# powerboard.net
KiCad netlist of a schematic drawn in EAGLE
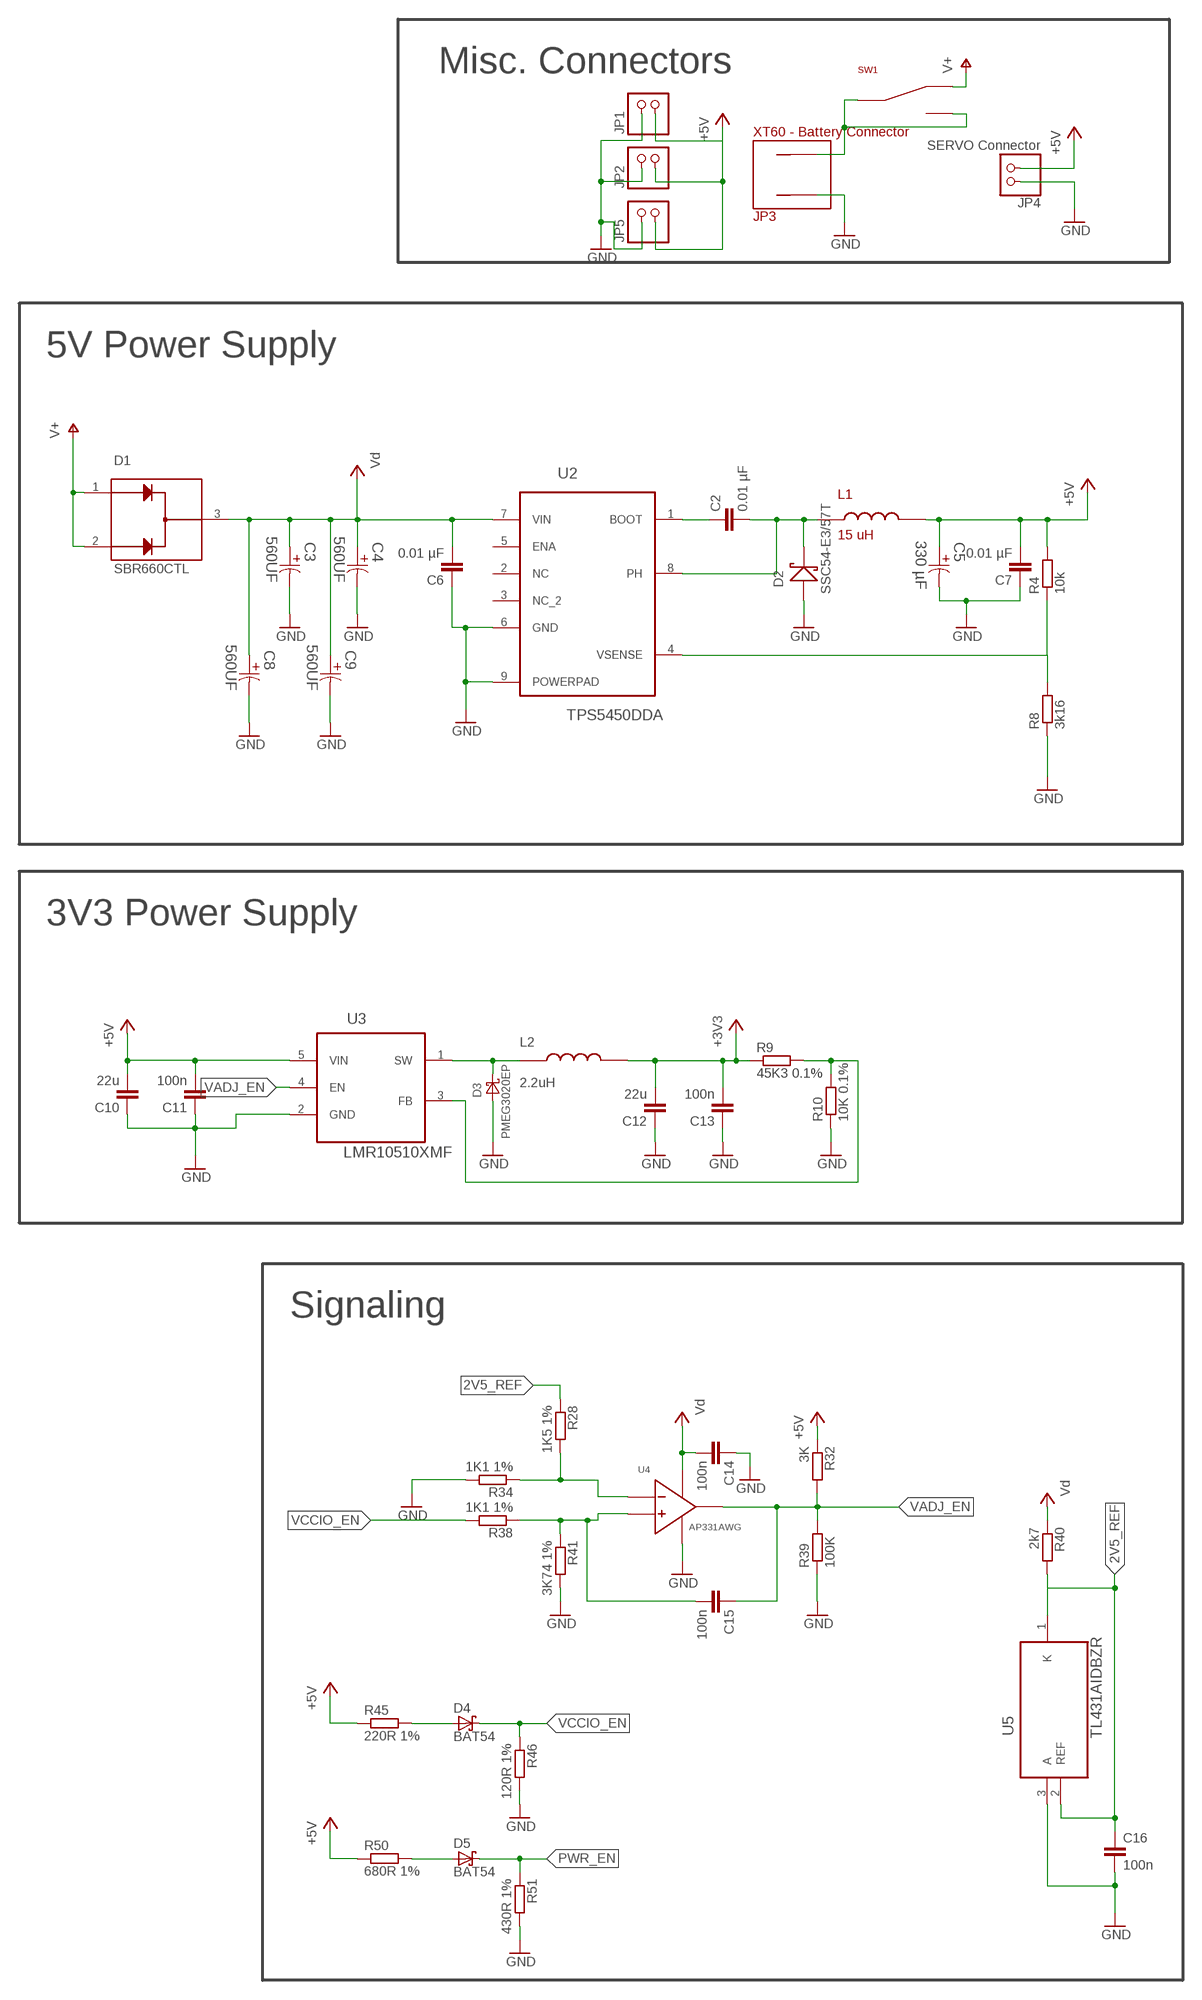
[diagram p0: schematic, sheet 1, part 1 of 2]
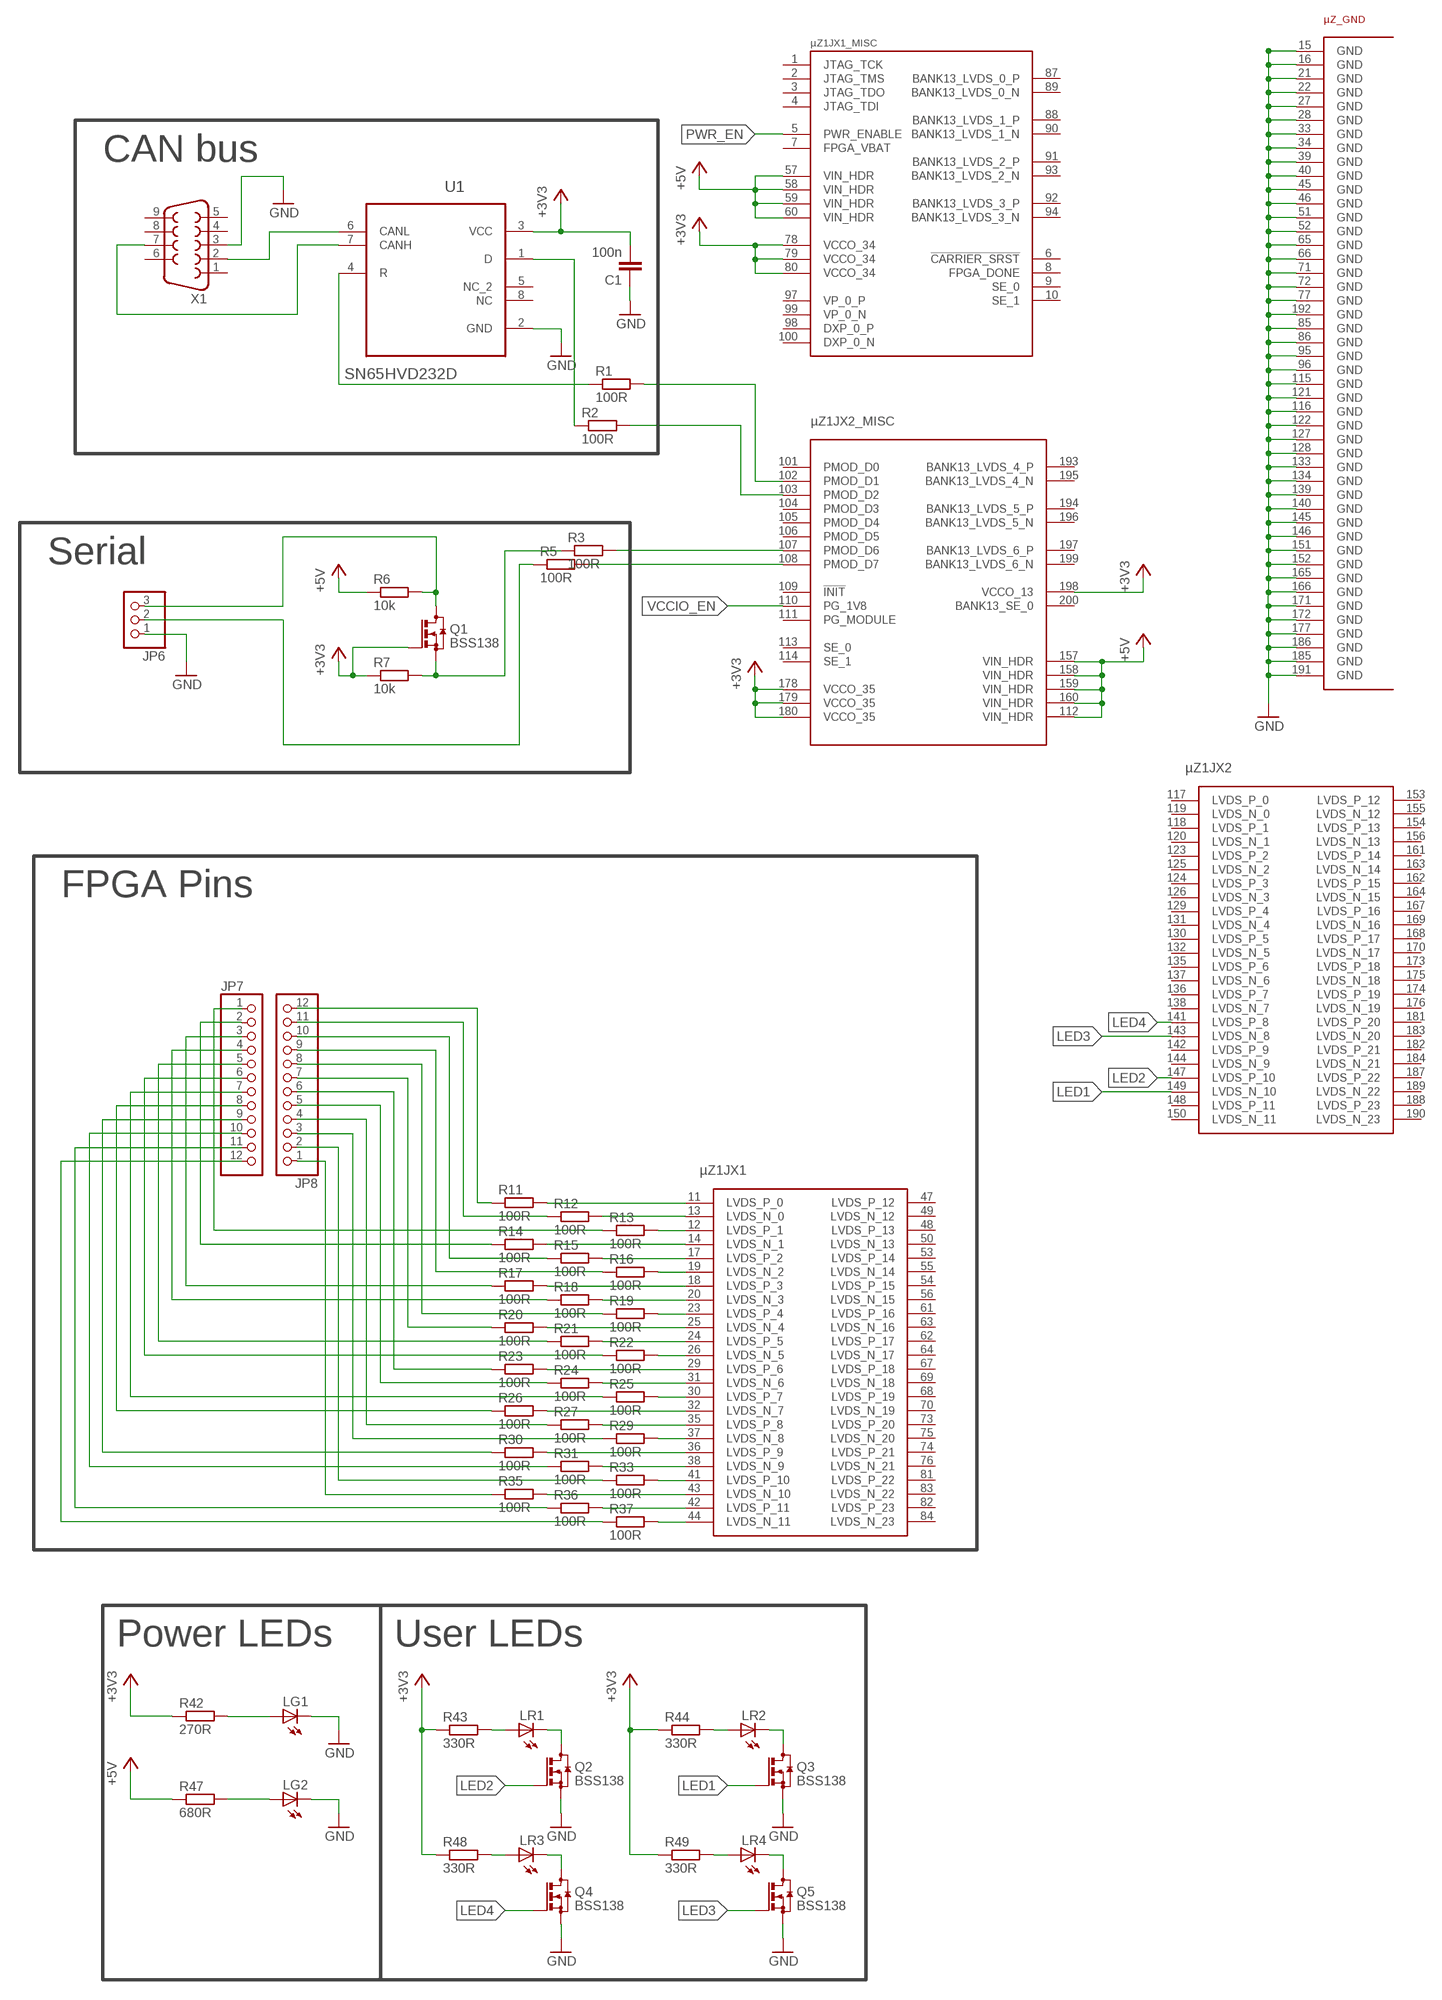
[diagram p1: schematic, sheet 1, part 2 of 2]

(export (version "E")
  (design (tool "Eeschema 10.0.6"))
  (components
    (comp (ref "C1")
      (value "100n")
      (footprint "eagle-import:C0805")
      (libsource (lib "eagle-import") (part "C-EUC0805"))
    )
    (comp (ref "C2")
      (value "0.01 µF")
      (footprint "eagle-import:C0805")
      (libsource (lib "eagle-import") (part "C-EUC0805"))
    )
    (comp (ref "C3")
      (value "560UF")
      (footprint "eagle-import:CAPAE1030X1050N")
      (fields (field (name "MPN") "EEE-FT1V561AP") (field (name "TOLERANCE") "±20 %"))
      (libsource (lib "eagle-import") (part "EEE--CASE-GFT1V561AP"))
    )
    (comp (ref "C4")
      (value "560UF")
      (footprint "eagle-import:CAPAE1030X1050N")
      (fields (field (name "MPN") "EEE-FT1V561AP") (field (name "TOLERANCE") "±20 %"))
      (libsource (lib "eagle-import") (part "EEE--CASE-GFT1V561AP"))
    )
    (comp (ref "C5")
      (value "330 µF")
      (footprint "eagle-import:CAPAE660X800N")
      (fields (field (name "MPN") "EEE-FTC331XAP") (field (name "TOLERANCE") "±20 %"))
      (libsource (lib "eagle-import") (part "EEE--CASE-D8FTC331XAP"))
    )
    (comp (ref "C6")
      (value "0.01 µF")
      (footprint "eagle-import:C0805")
      (libsource (lib "eagle-import") (part "C-EUC0805"))
    )
    (comp (ref "C7")
      (value "0.01 µF")
      (footprint "eagle-import:C0805")
      (libsource (lib "eagle-import") (part "C-EUC0805"))
    )
    (comp (ref "C8")
      (value "560UF")
      (footprint "eagle-import:CAPAE1030X1050N")
      (fields (field (name "MPN") "EEE-FT1V561AP") (field (name "TOLERANCE") "±20 %"))
      (libsource (lib "eagle-import") (part "EEE--CASE-GFT1V561AP"))
    )
    (comp (ref "C9")
      (value "560UF")
      (footprint "eagle-import:CAPAE1030X1050N")
      (fields (field (name "MPN") "EEE-FT1V561AP") (field (name "TOLERANCE") "±20 %"))
      (libsource (lib "eagle-import") (part "EEE--CASE-GFT1V561AP"))
    )
    (comp (ref "C10")
      (value "22u")
      (footprint "eagle-import:C0805")
      (libsource (lib "eagle-import") (part "C-EUC0805"))
    )
    (comp (ref "C11")
      (value "100n")
      (footprint "eagle-import:C0805")
      (libsource (lib "eagle-import") (part "C-EUC0805"))
    )
    (comp (ref "C12")
      (value "22u")
      (footprint "eagle-import:C0805")
      (libsource (lib "eagle-import") (part "C-EUC0805"))
    )
    (comp (ref "C13")
      (value "100n")
      (footprint "eagle-import:C0805")
      (libsource (lib "eagle-import") (part "C-EUC0805"))
    )
    (comp (ref "C14")
      (value "100n")
      (footprint "eagle-import:C0805")
      (libsource (lib "eagle-import") (part "C-EUC0805"))
    )
    (comp (ref "C15")
      (value "100n")
      (footprint "eagle-import:C0805")
      (libsource (lib "eagle-import") (part "C-EUC0805"))
    )
    (comp (ref "C16")
      (value "100n")
      (footprint "eagle-import:C0805")
      (libsource (lib "eagle-import") (part "C-EUC0805"))
    )
    (comp (ref "D1")
      (value "SBR660CTL")
      (footprint "eagle-import:TO252")
      (libsource (lib "eagle-import") (part "SBR660CTL"))
    )
    (comp (ref "D2")
      (value "SSC54-E3/57T")
      (footprint "eagle-import:DO-214AB")
      (fields (field (name "MANUFACTURER") "Comchip Technology") (field (name "PART_NUMBER") "CDBC540-G"))
      (libsource (lib "eagle-import") (part "CDBC540-G"))
    )
    (comp (ref "D3")
      (value "PMEG3020EP")
      (footprint "eagle-import:SOD128")
      (libsource (lib "eagle-import") (part "DIODE-SCHOTTKY-SOD128"))
    )
    (comp (ref "D4")
      (value "BAT54")
      (footprint "eagle-import:SOT23")
      (libsource (lib "eagle-import") (part "BAT54"))
    )
    (comp (ref "D5")
      (value "BAT54")
      (footprint "eagle-import:SOT23")
      (libsource (lib "eagle-import") (part "BAT54"))
    )
    (comp (ref "JP1")
      (value "PINHD-1X2")
      (footprint "eagle-import:CUST")
      (libsource (lib "eagle-import") (part "PINHD-1X2"))
    )
    (comp (ref "JP2")
      (value "PINHD-1X2")
      (footprint "eagle-import:CUST")
      (libsource (lib "eagle-import") (part "PINHD-1X2"))
    )
    (comp (ref "JP3")
      (value "XT60 - Battery Connector")
      (footprint "eagle-import:XT60")
      (libsource (lib "eagle-import") (part "XT60"))
    )
    (comp (ref "JP4")
      (value "SERVO Connector")
      (footprint "eagle-import:1X02_90")
      (libsource (lib "eagle-import") (part "PINHD-1X2/90"))
    )
    (comp (ref "JP5")
      (value "PINHD-1X2")
      (footprint "eagle-import:CUST")
      (libsource (lib "eagle-import") (part "PINHD-1X2"))
    )
    (comp (ref "JP6")
      (value "PINHD-1X3")
      (footprint "eagle-import:1X03")
      (libsource (lib "eagle-import") (part "PINHD-1X3"))
    )
    (comp (ref "JP7")
      (value "PINHD-1X12")
      (footprint "eagle-import:1X12")
      (libsource (lib "eagle-import") (part "PINHD-1X12"))
    )
    (comp (ref "JP8")
      (value "PINHD-1X12")
      (footprint "eagle-import:1X12")
      (libsource (lib "eagle-import") (part "PINHD-1X12"))
    )
    (comp (ref "L1")
      (value "15 uH")
      (footprint "eagle-import:BOURNS")
      (libsource (lib "eagle-import") (part "BOURNS-POWER-IND"))
    )
    (comp (ref "L2")
      (value "2.2uH")
      (footprint "eagle-import:INDZYNQ2")
      (libsource (lib "eagle-import") (part "INDZYNQNEW"))
    )
    (comp (ref "LG1")
      (value "LEDCHIP-LED0805")
      (footprint "eagle-import:CHIP-LED0805")
      (libsource (lib "eagle-import") (part "LEDCHIP-LED0805"))
    )
    (comp (ref "LG2")
      (value "LEDCHIP-LED0805")
      (footprint "eagle-import:CHIP-LED0805")
      (libsource (lib "eagle-import") (part "LEDCHIP-LED0805"))
    )
    (comp (ref "LR1")
      (value "LEDCHIP-LED0805")
      (footprint "eagle-import:CHIP-LED0805")
      (libsource (lib "eagle-import") (part "LEDCHIP-LED0805"))
    )
    (comp (ref "LR2")
      (value "LEDCHIP-LED0805")
      (footprint "eagle-import:CHIP-LED0805")
      (libsource (lib "eagle-import") (part "LEDCHIP-LED0805"))
    )
    (comp (ref "LR3")
      (value "LEDCHIP-LED0805")
      (footprint "eagle-import:CHIP-LED0805")
      (libsource (lib "eagle-import") (part "LEDCHIP-LED0805"))
    )
    (comp (ref "LR4")
      (value "LEDCHIP-LED0805")
      (footprint "eagle-import:CHIP-LED0805")
      (libsource (lib "eagle-import") (part "LEDCHIP-LED0805"))
    )
    (comp (ref "Q1")
      (value "BSS138")
      (footprint "eagle-import:SOT23")
      (libsource (lib "eagle-import") (part "BSS123"))
    )
    (comp (ref "Q2")
      (value "BSS138")
      (footprint "eagle-import:SOT23")
      (libsource (lib "eagle-import") (part "BSS123"))
    )
    (comp (ref "Q3")
      (value "BSS138")
      (footprint "eagle-import:SOT23")
      (libsource (lib "eagle-import") (part "BSS123"))
    )
    (comp (ref "Q4")
      (value "BSS138")
      (footprint "eagle-import:SOT23")
      (libsource (lib "eagle-import") (part "BSS123"))
    )
    (comp (ref "Q5")
      (value "BSS138")
      (footprint "eagle-import:SOT23")
      (libsource (lib "eagle-import") (part "BSS123"))
    )
    (comp (ref "R1")
      (value "100R")
      (footprint "eagle-import:R0805")
      (libsource (lib "eagle-import") (part "R-EU_R0805"))
    )
    (comp (ref "R2")
      (value "100R")
      (footprint "eagle-import:R0805")
      (libsource (lib "eagle-import") (part "R-EU_R0805"))
    )
    (comp (ref "R3")
      (value "100R")
      (footprint "eagle-import:R0805")
      (libsource (lib "eagle-import") (part "R-EU_R0805"))
    )
    (comp (ref "R4")
      (value "10k")
      (footprint "eagle-import:R0805")
      (libsource (lib "eagle-import") (part "R-EU_R0805"))
    )
    (comp (ref "R5")
      (value "100R")
      (footprint "eagle-import:R0805")
      (libsource (lib "eagle-import") (part "R-EU_R0805"))
    )
    (comp (ref "R6")
      (value "10k")
      (footprint "eagle-import:R0805")
      (libsource (lib "eagle-import") (part "R-EU_R0805"))
    )
    (comp (ref "R7")
      (value "10k")
      (footprint "eagle-import:R0805")
      (libsource (lib "eagle-import") (part "R-EU_R0805"))
    )
    (comp (ref "R8")
      (value "3k16")
      (footprint "eagle-import:R0805")
      (libsource (lib "eagle-import") (part "R-EU_R0805"))
    )
    (comp (ref "R9")
      (value "45K3 0.1%")
      (footprint "eagle-import:R0805")
      (libsource (lib "eagle-import") (part "R-EU_R0805"))
    )
    (comp (ref "R10")
      (value "10K 0.1%")
      (footprint "eagle-import:R0805")
      (libsource (lib "eagle-import") (part "R-EU_R0805"))
    )
    (comp (ref "R11")
      (value "100R")
      (footprint "eagle-import:R0805")
      (libsource (lib "eagle-import") (part "R-EU_R0805"))
    )
    (comp (ref "R12")
      (value "100R")
      (footprint "eagle-import:R0805")
      (libsource (lib "eagle-import") (part "R-EU_R0805"))
    )
    (comp (ref "R13")
      (value "100R")
      (footprint "eagle-import:R0805")
      (libsource (lib "eagle-import") (part "R-EU_R0805"))
    )
    (comp (ref "R14")
      (value "100R")
      (footprint "eagle-import:R0805")
      (libsource (lib "eagle-import") (part "R-EU_R0805"))
    )
    (comp (ref "R15")
      (value "100R")
      (footprint "eagle-import:R0805")
      (libsource (lib "eagle-import") (part "R-EU_R0805"))
    )
    (comp (ref "R16")
      (value "100R")
      (footprint "eagle-import:R0805")
      (libsource (lib "eagle-import") (part "R-EU_R0805"))
    )
    (comp (ref "R17")
      (value "100R")
      (footprint "eagle-import:R0805")
      (libsource (lib "eagle-import") (part "R-EU_R0805"))
    )
    (comp (ref "R18")
      (value "100R")
      (footprint "eagle-import:R0805")
      (libsource (lib "eagle-import") (part "R-EU_R0805"))
    )
    (comp (ref "R19")
      (value "100R")
      (footprint "eagle-import:R0805")
      (libsource (lib "eagle-import") (part "R-EU_R0805"))
    )
    (comp (ref "R20")
      (value "100R")
      (footprint "eagle-import:R0805")
      (libsource (lib "eagle-import") (part "R-EU_R0805"))
    )
    (comp (ref "R21")
      (value "100R")
      (footprint "eagle-import:R0805")
      (libsource (lib "eagle-import") (part "R-EU_R0805"))
    )
    (comp (ref "R22")
      (value "100R")
      (footprint "eagle-import:R0805")
      (libsource (lib "eagle-import") (part "R-EU_R0805"))
    )
    (comp (ref "R23")
      (value "100R")
      (footprint "eagle-import:R0805")
      (libsource (lib "eagle-import") (part "R-EU_R0805"))
    )
    (comp (ref "R24")
      (value "100R")
      (footprint "eagle-import:R0805")
      (libsource (lib "eagle-import") (part "R-EU_R0805"))
    )
    (comp (ref "R25")
      (value "100R")
      (footprint "eagle-import:R0805")
      (libsource (lib "eagle-import") (part "R-EU_R0805"))
    )
    (comp (ref "R26")
      (value "100R")
      (footprint "eagle-import:R0805")
      (libsource (lib "eagle-import") (part "R-EU_R0805"))
    )
    (comp (ref "R27")
      (value "100R")
      (footprint "eagle-import:R0805")
      (libsource (lib "eagle-import") (part "R-EU_R0805"))
    )
    (comp (ref "R28")
      (value "1K5 1%")
      (footprint "eagle-import:R0805")
      (libsource (lib "eagle-import") (part "R-EU_R0805"))
    )
    (comp (ref "R29")
      (value "100R")
      (footprint "eagle-import:R0805")
      (libsource (lib "eagle-import") (part "R-EU_R0805"))
    )
    (comp (ref "R30")
      (value "100R")
      (footprint "eagle-import:R0805")
      (libsource (lib "eagle-import") (part "R-EU_R0805"))
    )
    (comp (ref "R31")
      (value "100R")
      (footprint "eagle-import:R0805")
      (libsource (lib "eagle-import") (part "R-EU_R0805"))
    )
    (comp (ref "R32")
      (value "3K")
      (footprint "eagle-import:R0805")
      (libsource (lib "eagle-import") (part "R-EU_R0805"))
    )
    (comp (ref "R33")
      (value "100R")
      (footprint "eagle-import:R0805")
      (libsource (lib "eagle-import") (part "R-EU_R0805"))
    )
    (comp (ref "R34")
      (value "1K1 1%")
      (footprint "eagle-import:R0805")
      (libsource (lib "eagle-import") (part "R-EU_R0805"))
    )
    (comp (ref "R35")
      (value "100R")
      (footprint "eagle-import:R0805")
      (libsource (lib "eagle-import") (part "R-EU_R0805"))
    )
    (comp (ref "R36")
      (value "100R")
      (footprint "eagle-import:R0805")
      (libsource (lib "eagle-import") (part "R-EU_R0805"))
    )
    (comp (ref "R37")
      (value "100R")
      (footprint "eagle-import:R0805")
      (libsource (lib "eagle-import") (part "R-EU_R0805"))
    )
    (comp (ref "R38")
      (value "1K1 1%")
      (footprint "eagle-import:R0805")
      (libsource (lib "eagle-import") (part "R-EU_R0805"))
    )
    (comp (ref "R39")
      (value "100K")
      (footprint "eagle-import:R0805")
      (libsource (lib "eagle-import") (part "R-EU_R0805"))
    )
    (comp (ref "R40")
      (value "2k7")
      (footprint "eagle-import:R0805")
      (libsource (lib "eagle-import") (part "R-EU_R0805"))
    )
    (comp (ref "R41")
      (value "3K74 1%")
      (footprint "eagle-import:R0805")
      (libsource (lib "eagle-import") (part "R-EU_R0805"))
    )
    (comp (ref "R42")
      (value "270R")
      (footprint "eagle-import:R0805")
      (libsource (lib "eagle-import") (part "R-EU_R0805"))
    )
    (comp (ref "R43")
      (value "330R")
      (footprint "eagle-import:R0805")
      (libsource (lib "eagle-import") (part "R-EU_R0805"))
    )
    (comp (ref "R44")
      (value "330R")
      (footprint "eagle-import:R0805")
      (libsource (lib "eagle-import") (part "R-EU_R0805"))
    )
    (comp (ref "R45")
      (value "220R 1%")
      (footprint "eagle-import:R0805")
      (libsource (lib "eagle-import") (part "R-EU_R0805"))
    )
    (comp (ref "R46")
      (value "120R 1%")
      (footprint "eagle-import:R0805")
      (libsource (lib "eagle-import") (part "R-EU_R0805"))
    )
    (comp (ref "R47")
      (value "680R")
      (footprint "eagle-import:R0805")
      (libsource (lib "eagle-import") (part "R-EU_R0805"))
    )
    (comp (ref "R48")
      (value "330R")
      (footprint "eagle-import:R0805")
      (libsource (lib "eagle-import") (part "R-EU_R0805"))
    )
    (comp (ref "R49")
      (value "330R")
      (footprint "eagle-import:R0805")
      (libsource (lib "eagle-import") (part "R-EU_R0805"))
    )
    (comp (ref "R50")
      (value "680R 1%")
      (footprint "eagle-import:R0805")
      (libsource (lib "eagle-import") (part "R-EU_R0805"))
    )
    (comp (ref "R51")
      (value "430R 1%")
      (footprint "eagle-import:R0805")
      (libsource (lib "eagle-import") (part "R-EU_R0805"))
    )
    (comp (ref "SW1") (value "SW") (footprint "eagle-import:SW") (libsource (lib "eagle-import") (part "SW")))
    (comp (ref "U1")
      (value "SN65HVD232D")
      (footprint "eagle-import:SOIC127P600X175-8N")
      (libsource (lib "eagle-import") (part "SN65HVD232D"))
    )
    (comp (ref "U2")
      (value "TPS5450DDA")
      (footprint "eagle-import:SOIC127P600X170-9N")
      (libsource (lib "eagle-import") (part "TPS5450DDA"))
    )
    (comp (ref "U3")
      (value "LMR10510XMF")
      (footprint "eagle-import:SOT95P290X145-5N")
      (libsource (lib "eagle-import") (part "LMR10510XMF"))
    )
    (comp (ref "U4")
      (value "AP331AWG")
      (footprint "eagle-import:SOT95P290X145-5N")
      (libsource (lib "eagle-import") (part "AP331AWG"))
    )
    (comp (ref "U5")
      (value "TL431AIDBZR")
      (footprint "eagle-import:SOT95P230X110-3N")
      (libsource (lib "eagle-import") (part "TL431AIDBZR"))
    )
    (comp (ref "X1")
      (value "F09HP")
      (footprint "eagle-import:F09HP")
      (libsource (lib "eagle-import") (part "F09HP"))
    )
    (comp (ref "µZ1")
      (value "µZTS")
      (footprint "eagle-import:µZ_E")
      (fields
        (field (name "LINK") "http://cz.farnell.com/fci/61083-104400lf/plug-smd-0-8mm-100way/dp/1103987")
      )
      (libsource (lib "eagle-import") (part "µZTS"))
    )
  )
  (nets
    (net (code "1") (name "+3V3") (class "Default")
      (node (ref "C1") (pin "2") (pinfunction "2_2") (pintype "passive"))
      (node (ref "C12") (pin "2") (pinfunction "2_2") (pintype "passive"))
      (node (ref "C13") (pin "2") (pinfunction "2_2") (pintype "passive"))
      (node (ref "L2") (pin "P$2") (pinfunction "P$2_P$2") (pintype "bidirectional"))
      (node (ref "Q1") (pin "1") (pinfunction "G_1") (pintype "passive"))
      (node (ref "R42") (pin "1") (pinfunction "1_1") (pintype "passive"))
      (node (ref "R43") (pin "1") (pinfunction "1_1") (pintype "passive"))
      (node (ref "R44") (pin "1") (pinfunction "1_1") (pintype "passive"))
      (node (ref "R48") (pin "1") (pinfunction "1_1") (pintype "passive"))
      (node (ref "R49") (pin "1") (pinfunction "1_1") (pintype "passive"))
      (node (ref "R7") (pin "1") (pinfunction "1_1") (pintype "passive"))
      (node (ref "R9") (pin "1") (pinfunction "1_1") (pintype "passive"))
      (node (ref "U1") (pin "3") (pinfunction "VCC_3") (pintype "power_in"))
      (node (ref "µZ1") (pin "178") (pinfunction "VCCO_35_178") (pintype "power_in"))
      (node (ref "µZ1") (pin "179") (pinfunction "VCCO_35_179") (pintype "power_in"))
      (node (ref "µZ1") (pin "180") (pinfunction "VCCO_35_180") (pintype "power_in"))
      (node (ref "µZ1") (pin "198") (pinfunction "VCCO_13_198") (pintype "power_in"))
      (node (ref "µZ1") (pin "78") (pinfunction "VCCO_34_78") (pintype "power_in"))
      (node (ref "µZ1") (pin "79") (pinfunction "VCCO_34_79") (pintype "power_in"))
      (node (ref "µZ1") (pin "80") (pinfunction "VCCO_34_80") (pintype "power_in"))
    )
    (net (code "2") (name "+5V") (class "Default")
      (node (ref "C10") (pin "2") (pinfunction "2_2") (pintype "passive"))
      (node (ref "C11") (pin "2") (pinfunction "2_2") (pintype "passive"))
      (node (ref "C5") (pin "1") (pinfunction "1_1") (pintype "passive"))
      (node (ref "C7") (pin "2") (pinfunction "2_2") (pintype "passive"))
      (node (ref "JP1") (pin "P$2") (pinfunction "2_P$2") (pintype "passive"))
      (node (ref "JP2") (pin "P$2") (pinfunction "2_P$2") (pintype "passive"))
      (node (ref "JP4") (pin "2") (pinfunction "2_2") (pintype "passive"))
      (node (ref "JP5") (pin "P$2") (pinfunction "2_P$2") (pintype "passive"))
      (node (ref "L1") (pin "P$2") (pinfunction "P$2_P$2") (pintype "bidirectional"))
      (node (ref "R32") (pin "1") (pinfunction "1_1") (pintype "passive"))
      (node (ref "R4") (pin "2") (pinfunction "2_2") (pintype "passive"))
      (node (ref "R45") (pin "1") (pinfunction "1_1") (pintype "passive"))
      (node (ref "R47") (pin "1") (pinfunction "1_1") (pintype "passive"))
      (node (ref "R50") (pin "1") (pinfunction "1_1") (pintype "passive"))
      (node (ref "R6") (pin "1") (pinfunction "1_1") (pintype "passive"))
      (node (ref "U3") (pin "5") (pinfunction "VIN_5") (pintype "power_in"))
      (node (ref "µZ1") (pin "112") (pinfunction "VIN_HDR_112") (pintype "power_in"))
      (node (ref "µZ1") (pin "157") (pinfunction "VIN_HDR_157") (pintype "power_in"))
      (node (ref "µZ1") (pin "158") (pinfunction "VIN_HDR_158") (pintype "power_in"))
      (node (ref "µZ1") (pin "159") (pinfunction "VIN_HDR_159") (pintype "power_in"))
      (node (ref "µZ1") (pin "160") (pinfunction "VIN_HDR_160") (pintype "power_in"))
      (node (ref "µZ1") (pin "57") (pinfunction "VIN_HDR_57") (pintype "power_in"))
      (node (ref "µZ1") (pin "58") (pinfunction "VIN_HDR_58") (pintype "power_in"))
      (node (ref "µZ1") (pin "59") (pinfunction "VIN_HDR_59") (pintype "power_in"))
      (node (ref "µZ1") (pin "60") (pinfunction "VIN_HDR_60") (pintype "power_in"))
    )
    (net (code "3") (name "/FPGA_VBAT") (class "Default")
      (node (ref "µZ1") (pin "7") (pinfunction "FPGA_VBAT_7") (pintype "power_in"))
    )
    (net (code "4") (name "2V5_REF") (class "Default")
      (node (ref "C16") (pin "1") (pinfunction "1_1") (pintype "passive"))
      (node (ref "R28") (pin "1") (pinfunction "1_1") (pintype "passive"))
      (node (ref "R40") (pin "2") (pinfunction "2_2") (pintype "passive"))
      (node (ref "U5") (pin "1") (pinfunction "K_1") (pintype "passive"))
      (node (ref "U5") (pin "2") (pinfunction "REF_2") (pintype "passive"))
    )
    (net (code "5") (name "GND") (class "Default")
      (node (ref "C1") (pin "1") (pinfunction "1_1") (pintype "passive"))
      (node (ref "C10") (pin "1") (pinfunction "1_1") (pintype "passive"))
      (node (ref "C11") (pin "1") (pinfunction "1_1") (pintype "passive"))
      (node (ref "C12") (pin "1") (pinfunction "1_1") (pintype "passive"))
      (node (ref "C13") (pin "1") (pinfunction "1_1") (pintype "passive"))
      (node (ref "C14") (pin "1") (pinfunction "1_1") (pintype "passive"))
      (node (ref "C16") (pin "2") (pinfunction "2_2") (pintype "passive"))
      (node (ref "C3") (pin "2") (pinfunction "2_2") (pintype "passive"))
      (node (ref "C4") (pin "2") (pinfunction "2_2") (pintype "passive"))
      (node (ref "C5") (pin "2") (pinfunction "2_2") (pintype "passive"))
      (node (ref "C6") (pin "1") (pinfunction "1_1") (pintype "passive"))
      (node (ref "C7") (pin "1") (pinfunction "1_1") (pintype "passive"))
      (node (ref "C8") (pin "2") (pinfunction "2_2") (pintype "passive"))
      (node (ref "C9") (pin "2") (pinfunction "2_2") (pintype "passive"))
      (node (ref "D2") (pin "A") (pinfunction "A_A") (pintype "passive"))
      (node (ref "D3") (pin "A") (pinfunction "A_A") (pintype "passive"))
      (node (ref "JP1") (pin "P$1") (pinfunction "1_P$1") (pintype "passive"))
      (node (ref "JP2") (pin "P$1") (pinfunction "1_P$1") (pintype "passive"))
      (node (ref "JP3") (pin "P$2") (pinfunction "PLUS_P$2") (pintype "bidirectional"))
      (node (ref "JP4") (pin "1") (pinfunction "1_1") (pintype "passive"))
      (node (ref "JP5") (pin "P$1") (pinfunction "1_P$1") (pintype "passive"))
      (node (ref "JP6") (pin "1") (pinfunction "1_1") (pintype "passive"))
      (node (ref "LG1") (pin "C") (pinfunction "C_C") (pintype "passive"))
      (node (ref "LG2") (pin "C") (pinfunction "C_C") (pintype "passive"))
      (node (ref "Q2") (pin "2") (pinfunction "S_2") (pintype "passive"))
      (node (ref "Q3") (pin "2") (pinfunction "S_2") (pintype "passive"))
      (node (ref "Q4") (pin "2") (pinfunction "S_2") (pintype "passive"))
      (node (ref "Q5") (pin "2") (pinfunction "S_2") (pintype "passive"))
      (node (ref "R10") (pin "1") (pinfunction "1_1") (pintype "passive"))
      (node (ref "R34") (pin "2") (pinfunction "2_2") (pintype "passive"))
      (node (ref "R39") (pin "1") (pinfunction "1_1") (pintype "passive"))
      (node (ref "R41") (pin "2") (pinfunction "2_2") (pintype "passive"))
      (node (ref "R46") (pin "2") (pinfunction "2_2") (pintype "passive"))
      (node (ref "R51") (pin "2") (pinfunction "2_2") (pintype "passive"))
      (node (ref "R8") (pin "1") (pinfunction "1_1") (pintype "passive"))
      (node (ref "U1") (pin "2") (pinfunction "GND_2") (pintype "passive"))
      (node (ref "U2") (pin "6") (pinfunction "GND_6") (pintype "passive"))
      (node (ref "U2") (pin "9") (pinfunction "POWERPAD_9") (pintype "passive"))
      (node (ref "U3") (pin "2") (pinfunction "GND_2") (pintype "passive"))
      (node (ref "U4") (pin "2") (pinfunction "GND_2") (pintype "bidirectional"))
      (node (ref "U5") (pin "3") (pinfunction "A_3") (pintype "passive"))
      (node (ref "X1") (pin "3") (pinfunction "3_3") (pintype "passive"))
      (node (ref "µZ1") (pin "115") (pinfunction "GND_115") (pintype "power_in"))
      (node (ref "µZ1") (pin "116") (pinfunction "GND_116") (pintype "power_in"))
      (node (ref "µZ1") (pin "121") (pinfunction "GND_121") (pintype "power_in"))
      (node (ref "µZ1") (pin "122") (pinfunction "GND_122") (pintype "power_in"))
      (node (ref "µZ1") (pin "127") (pinfunction "GND_127") (pintype "power_in"))
      (node (ref "µZ1") (pin "128") (pinfunction "GND_128") (pintype "power_in"))
      (node (ref "µZ1") (pin "133") (pinfunction "GND_133") (pintype "power_in"))
      (node (ref "µZ1") (pin "134") (pinfunction "GND_134") (pintype "power_in"))
      (node (ref "µZ1") (pin "139") (pinfunction "GND_139") (pintype "power_in"))
      (node (ref "µZ1") (pin "140") (pinfunction "GND_140") (pintype "power_in"))
      (node (ref "µZ1") (pin "145") (pinfunction "GND_145") (pintype "power_in"))
      (node (ref "µZ1") (pin "146") (pinfunction "GND_146") (pintype "power_in"))
      (node (ref "µZ1") (pin "15") (pinfunction "GND_15") (pintype "power_in"))
      (node (ref "µZ1") (pin "151") (pinfunction "GND_151") (pintype "power_in"))
      (node (ref "µZ1") (pin "152") (pinfunction "GND_152") (pintype "power_in"))
      (node (ref "µZ1") (pin "16") (pinfunction "GND_16") (pintype "power_in"))
      (node (ref "µZ1") (pin "165") (pinfunction "GND_165") (pintype "power_in"))
      (node (ref "µZ1") (pin "166") (pinfunction "GND_166") (pintype "power_in"))
      (node (ref "µZ1") (pin "171") (pinfunction "GND_171") (pintype "power_in"))
      (node (ref "µZ1") (pin "172") (pinfunction "GND_172") (pintype "power_in"))
      (node (ref "µZ1") (pin "177") (pinfunction "GND_177") (pintype "power_in"))
      (node (ref "µZ1") (pin "185") (pinfunction "GND_185") (pintype "power_in"))
      (node (ref "µZ1") (pin "186") (pinfunction "GND_186") (pintype "power_in"))
      (node (ref "µZ1") (pin "191") (pinfunction "GND_191") (pintype "power_in"))
      (node (ref "µZ1") (pin "192") (pinfunction "GND_192") (pintype "power_in"))
      (node (ref "µZ1") (pin "21") (pinfunction "GND_21") (pintype "power_in"))
      (node (ref "µZ1") (pin "22") (pinfunction "GND_22") (pintype "power_in"))
      (node (ref "µZ1") (pin "27") (pinfunction "GND_27") (pintype "power_in"))
      (node (ref "µZ1") (pin "28") (pinfunction "GND_28") (pintype "power_in"))
      (node (ref "µZ1") (pin "33") (pinfunction "GND_33") (pintype "power_in"))
      (node (ref "µZ1") (pin "34") (pinfunction "GND_34") (pintype "power_in"))
      (node (ref "µZ1") (pin "39") (pinfunction "GND_39") (pintype "power_in"))
      (node (ref "µZ1") (pin "40") (pinfunction "GND_40") (pintype "power_in"))
      (node (ref "µZ1") (pin "45") (pinfunction "GND_45") (pintype "power_in"))
      (node (ref "µZ1") (pin "46") (pinfunction "GND_46") (pintype "power_in"))
      (node (ref "µZ1") (pin "51") (pinfunction "GND_51") (pintype "power_in"))
      (node (ref "µZ1") (pin "52") (pinfunction "GND_52") (pintype "power_in"))
      (node (ref "µZ1") (pin "65") (pinfunction "GND_65") (pintype "power_in"))
      (node (ref "µZ1") (pin "66") (pinfunction "GND_66") (pintype "power_in"))
      (node (ref "µZ1") (pin "71") (pinfunction "GND_71") (pintype "power_in"))
      (node (ref "µZ1") (pin "72") (pinfunction "GND_72") (pintype "power_in"))
      (node (ref "µZ1") (pin "77") (pinfunction "GND_77") (pintype "power_in"))
      (node (ref "µZ1") (pin "85") (pinfunction "GND_85") (pintype "power_in"))
      (node (ref "µZ1") (pin "86") (pinfunction "GND_86") (pintype "power_in"))
      (node (ref "µZ1") (pin "95") (pinfunction "GND_95") (pintype "power_in"))
      (node (ref "µZ1") (pin "96") (pinfunction "GND_96") (pintype "power_in"))
    )
    (net (code "6") (name "LED1") (class "Default")
      (node (ref "Q3") (pin "1") (pinfunction "G_1") (pintype "passive"))
      (node (ref "µZ1") (pin "149") (pinfunction "LVDS_N_10_149") (pintype "bidirectional"))
    )
    (net (code "7") (name "LED2") (class "Default")
      (node (ref "Q2") (pin "1") (pinfunction "G_1") (pintype "passive"))
      (node (ref "µZ1") (pin "147") (pinfunction "LVDS_P_10_147") (pintype "bidirectional"))
    )
    (net (code "8") (name "LED3") (class "Default")
      (node (ref "Q5") (pin "1") (pinfunction "G_1") (pintype "passive"))
      (node (ref "µZ1") (pin "143") (pinfunction "LVDS_N_8_143") (pintype "bidirectional"))
    )
    (net (code "9") (name "LED4") (class "Default")
      (node (ref "Q4") (pin "1") (pinfunction "G_1") (pintype "passive"))
      (node (ref "µZ1") (pin "141") (pinfunction "LVDS_P_8_141") (pintype "bidirectional"))
    )
    (net (code "10") (name "Net-(D4-A)") (class "Default")
      (node (ref "D4") (pin "1") (pinfunction "A_1") (pintype "passive"))
      (node (ref "R45") (pin "2") (pinfunction "2_2") (pintype "passive"))
    )
    (net (code "11") (name "Net-(D5-A)") (class "Default")
      (node (ref "D5") (pin "1") (pinfunction "A_1") (pintype "passive"))
      (node (ref "R50") (pin "2") (pinfunction "2_2") (pintype "passive"))
    )
    (net (code "12") (name "Net-(JP3-MINUS)") (class "Default")
      (node (ref "JP3") (pin "P$1") (pinfunction "MINUS_P$1") (pintype "bidirectional"))
      (node (ref "SW1") (pin "P$1") (pinfunction "P$1_P$1") (pintype "bidirectional"))
      (node (ref "SW1") (pin "P$3") (pinfunction "P$3_P$3") (pintype "bidirectional"))
    )
    (net (code "13") (name "Net-(JP6-Pad2)") (class "Default")
      (node (ref "JP6") (pin "2") (pinfunction "2_2") (pintype "passive"))
      (node (ref "R5") (pin "1") (pinfunction "1_1") (pintype "passive"))
    )
    (net (code "14") (name "Net-(JP7-Pad1)") (class "Default")
      (node (ref "JP7") (pin "1") (pinfunction "1_1") (pintype "passive"))
      (node (ref "R13") (pin "1") (pinfunction "1_1") (pintype "passive"))
    )
    (net (code "15") (name "Net-(JP7-Pad2)") (class "Default")
      (node (ref "JP7") (pin "2") (pinfunction "2_2") (pintype "passive"))
      (node (ref "R14") (pin "1") (pinfunction "1_1") (pintype "passive"))
    )
    (net (code "16") (name "Net-(JP7-Pad3)") (class "Default")
      (node (ref "JP7") (pin "3") (pinfunction "3_3") (pintype "passive"))
      (node (ref "R17") (pin "1") (pinfunction "1_1") (pintype "passive"))
    )
    (net (code "17") (name "Net-(JP7-Pad4)") (class "Default")
      (node (ref "JP7") (pin "4") (pinfunction "4_4") (pintype "passive"))
      (node (ref "R18") (pin "1") (pinfunction "1_1") (pintype "passive"))
    )
    (net (code "18") (name "Net-(JP7-Pad5)") (class "Default")
      (node (ref "JP7") (pin "5") (pinfunction "5_5") (pintype "passive"))
      (node (ref "R21") (pin "1") (pinfunction "1_1") (pintype "passive"))
    )
    (net (code "19") (name "Net-(JP7-Pad6)") (class "Default")
      (node (ref "JP7") (pin "6") (pinfunction "6_6") (pintype "passive"))
      (node (ref "R22") (pin "1") (pinfunction "1_1") (pintype "passive"))
    )
    (net (code "20") (name "Net-(JP7-Pad7)") (class "Default")
      (node (ref "JP7") (pin "7") (pinfunction "7_7") (pintype "passive"))
      (node (ref "R25") (pin "1") (pinfunction "1_1") (pintype "passive"))
    )
    (net (code "21") (name "Net-(JP7-Pad8)") (class "Default")
      (node (ref "JP7") (pin "8") (pinfunction "8_8") (pintype "passive"))
      (node (ref "R26") (pin "1") (pinfunction "1_1") (pintype "passive"))
    )
    (net (code "22") (name "Net-(JP7-Pad9)") (class "Default")
      (node (ref "JP7") (pin "9") (pinfunction "9_9") (pintype "passive"))
      (node (ref "R30") (pin "1") (pinfunction "1_1") (pintype "passive"))
    )
    (net (code "23") (name "Net-(JP7-Pad10)") (class "Default")
      (node (ref "JP7") (pin "10") (pinfunction "10_10") (pintype "passive"))
      (node (ref "R31") (pin "1") (pinfunction "1_1") (pintype "passive"))
    )
    (net (code "24") (name "Net-(JP7-Pad11)") (class "Default")
      (node (ref "JP7") (pin "11") (pinfunction "11_11") (pintype "passive"))
      (node (ref "R36") (pin "1") (pinfunction "1_1") (pintype "passive"))
    )
    (net (code "25") (name "Net-(JP7-Pad12)") (class "Default")
      (node (ref "JP7") (pin "12") (pinfunction "12_12") (pintype "passive"))
      (node (ref "R37") (pin "1") (pinfunction "1_1") (pintype "passive"))
    )
    (net (code "26") (name "Net-(JP8-Pad1)") (class "Default")
      (node (ref "JP8") (pin "1") (pinfunction "1_1") (pintype "passive"))
      (node (ref "R35") (pin "1") (pinfunction "1_1") (pintype "passive"))
    )
    (net (code "27") (name "Net-(JP8-Pad2)") (class "Default")
      (node (ref "JP8") (pin "2") (pinfunction "2_2") (pintype "passive"))
      (node (ref "R33") (pin "1") (pinfunction "1_1") (pintype "passive"))
    )
    (net (code "28") (name "Net-(JP8-Pad3)") (class "Default")
      (node (ref "JP8") (pin "3") (pinfunction "3_3") (pintype "passive"))
      (node (ref "R29") (pin "1") (pinfunction "1_1") (pintype "passive"))
    )
    (net (code "29") (name "Net-(JP8-Pad4)") (class "Default")
      (node (ref "JP8") (pin "4") (pinfunction "4_4") (pintype "passive"))
      (node (ref "R27") (pin "1") (pinfunction "1_1") (pintype "passive"))
    )
    (net (code "30") (name "Net-(JP8-Pad5)") (class "Default")
      (node (ref "JP8") (pin "5") (pinfunction "5_5") (pintype "passive"))
      (node (ref "R24") (pin "1") (pinfunction "1_1") (pintype "passive"))
    )
    (net (code "31") (name "Net-(JP8-Pad6)") (class "Default")
      (node (ref "JP8") (pin "6") (pinfunction "6_6") (pintype "passive"))
      (node (ref "R23") (pin "1") (pinfunction "1_1") (pintype "passive"))
    )
    (net (code "32") (name "Net-(JP8-Pad7)") (class "Default")
      (node (ref "JP8") (pin "7") (pinfunction "7_7") (pintype "passive"))
      (node (ref "R20") (pin "1") (pinfunction "1_1") (pintype "passive"))
    )
    (net (code "33") (name "Net-(JP8-Pad8)") (class "Default")
      (node (ref "JP8") (pin "8") (pinfunction "8_8") (pintype "passive"))
      (node (ref "R19") (pin "1") (pinfunction "1_1") (pintype "passive"))
    )
    (net (code "34") (name "Net-(JP8-Pad9)") (class "Default")
      (node (ref "JP8") (pin "9") (pinfunction "9_9") (pintype "passive"))
      (node (ref "R16") (pin "1") (pinfunction "1_1") (pintype "passive"))
    )
    (net (code "35") (name "Net-(JP8-Pad10)") (class "Default")
      (node (ref "JP8") (pin "10") (pinfunction "10_10") (pintype "passive"))
      (node (ref "R15") (pin "1") (pinfunction "1_1") (pintype "passive"))
    )
    (net (code "36") (name "Net-(JP8-Pad11)") (class "Default")
      (node (ref "JP8") (pin "11") (pinfunction "11_11") (pintype "passive"))
      (node (ref "R12") (pin "1") (pinfunction "1_1") (pintype "passive"))
    )
    (net (code "37") (name "Net-(JP8-Pad12)") (class "Default")
      (node (ref "JP8") (pin "12") (pinfunction "12_12") (pintype "passive"))
      (node (ref "R11") (pin "1") (pinfunction "1_1") (pintype "passive"))
    )
    (net (code "38") (name "Net-(LG1-PadA)") (class "Default")
      (node (ref "LG1") (pin "A") (pinfunction "A_A") (pintype "passive"))
      (node (ref "R42") (pin "2") (pinfunction "2_2") (pintype "passive"))
    )
    (net (code "39") (name "Net-(LG2-PadA)") (class "Default")
      (node (ref "LG2") (pin "A") (pinfunction "A_A") (pintype "passive"))
      (node (ref "R47") (pin "2") (pinfunction "2_2") (pintype "passive"))
    )
    (net (code "40") (name "Net-(LR1-PadA)") (class "Default")
      (node (ref "LR1") (pin "A") (pinfunction "A_A") (pintype "passive"))
      (node (ref "R43") (pin "2") (pinfunction "2_2") (pintype "passive"))
    )
    (net (code "41") (name "Net-(LR2-PadA)") (class "Default")
      (node (ref "LR2") (pin "A") (pinfunction "A_A") (pintype "passive"))
      (node (ref "R44") (pin "2") (pinfunction "2_2") (pintype "passive"))
    )
    (net (code "42") (name "Net-(LR3-PadA)") (class "Default")
      (node (ref "LR3") (pin "A") (pinfunction "A_A") (pintype "passive"))
      (node (ref "R48") (pin "2") (pinfunction "2_2") (pintype "passive"))
    )
    (net (code "43") (name "Net-(LR4-PadA)") (class "Default")
      (node (ref "LR4") (pin "A") (pinfunction "A_A") (pintype "passive"))
      (node (ref "R49") (pin "2") (pinfunction "2_2") (pintype "passive"))
    )
    (net (code "44") (name "Net-(Q1-D)") (class "Default")
      (node (ref "JP6") (pin "3") (pinfunction "3_3") (pintype "passive"))
      (node (ref "Q1") (pin "3") (pinfunction "D_3") (pintype "passive"))
      (node (ref "R6") (pin "2") (pinfunction "2_2") (pintype "passive"))
    )
    (net (code "45") (name "Net-(Q1-S)") (class "Default")
      (node (ref "Q1") (pin "2") (pinfunction "S_2") (pintype "passive"))
      (node (ref "R3") (pin "1") (pinfunction "1_1") (pintype "passive"))
      (node (ref "R7") (pin "2") (pinfunction "2_2") (pintype "passive"))
    )
    (net (code "46") (name "Net-(Q2-D)") (class "Default")
      (node (ref "LR1") (pin "C") (pinfunction "C_C") (pintype "passive"))
      (node (ref "Q2") (pin "3") (pinfunction "D_3") (pintype "passive"))
    )
    (net (code "47") (name "Net-(Q3-D)") (class "Default")
      (node (ref "LR2") (pin "C") (pinfunction "C_C") (pintype "passive"))
      (node (ref "Q3") (pin "3") (pinfunction "D_3") (pintype "passive"))
    )
    (net (code "48") (name "Net-(Q4-D)") (class "Default")
      (node (ref "LR3") (pin "C") (pinfunction "C_C") (pintype "passive"))
      (node (ref "Q4") (pin "3") (pinfunction "D_3") (pintype "passive"))
    )
    (net (code "49") (name "Net-(Q5-D)") (class "Default")
      (node (ref "LR4") (pin "C") (pinfunction "C_C") (pintype "passive"))
      (node (ref "Q5") (pin "3") (pinfunction "D_3") (pintype "passive"))
    )
    (net (code "50") (name "Net-(U1-CANH)") (class "Default")
      (node (ref "U1") (pin "7") (pinfunction "CANH_7") (pintype "output"))
      (node (ref "X1") (pin "7") (pinfunction "7_7") (pintype "passive"))
    )
    (net (code "51") (name "Net-(U1-CANL)") (class "Default")
      (node (ref "U1") (pin "6") (pinfunction "CANL_6") (pintype "output"))
      (node (ref "X1") (pin "2") (pinfunction "2_2") (pintype "passive"))
    )
    (net (code "52") (name "Net-(U1-D)") (class "Default")
      (node (ref "R2") (pin "1") (pinfunction "1_1") (pintype "passive"))
      (node (ref "U1") (pin "1") (pinfunction "D_1") (pintype "input"))
    )
    (net (code "53") (name "Net-(U1-R)") (class "Default")
      (node (ref "R1") (pin "1") (pinfunction "1_1") (pintype "passive"))
      (node (ref "U1") (pin "4") (pinfunction "R_4") (pintype "output"))
    )
    (net (code "54") (name "Net-(U2-BOOT)") (class "Default")
      (node (ref "C2") (pin "1") (pinfunction "1_1") (pintype "passive"))
      (node (ref "U2") (pin "1") (pinfunction "BOOT_1") (pintype "input"))
    )
    (net (code "55") (name "Net-(U2-PH)") (class "Default")
      (node (ref "C2") (pin "2") (pinfunction "2_2") (pintype "passive"))
      (node (ref "D2") (pin "C") (pinfunction "C_C") (pintype "passive"))
      (node (ref "L1") (pin "P$1") (pinfunction "P$1_P$1") (pintype "bidirectional"))
      (node (ref "U2") (pin "8") (pinfunction "PH_8") (pintype "output"))
    )
    (net (code "56") (name "Net-(U2-VSENSE)") (class "Default")
      (node (ref "R4") (pin "1") (pinfunction "1_1") (pintype "passive"))
      (node (ref "R8") (pin "2") (pinfunction "2_2") (pintype "passive"))
      (node (ref "U2") (pin "4") (pinfunction "VSENSE_4") (pintype "input"))
    )
    (net (code "57") (name "Net-(U3-FB)") (class "Default")
      (node (ref "R10") (pin "2") (pinfunction "2_2") (pintype "passive"))
      (node (ref "R9") (pin "2") (pinfunction "2_2") (pintype "passive"))
      (node (ref "U3") (pin "3") (pinfunction "FB_3") (pintype "input"))
    )
    (net (code "58") (name "Net-(U3-SW)") (class "Default")
      (node (ref "D3") (pin "C") (pinfunction "C_C") (pintype "passive"))
      (node (ref "L2") (pin "P$1") (pinfunction "P$1_P$1") (pintype "bidirectional"))
      (node (ref "U3") (pin "1") (pinfunction "SW_1") (pintype "passive"))
    )
    (net (code "59") (name "Net-(U4-IN+)") (class "Default")
      (node (ref "C15") (pin "2") (pinfunction "2_2") (pintype "passive"))
      (node (ref "R38") (pin "1") (pinfunction "1_1") (pintype "passive"))
      (node (ref "R41") (pin "1") (pinfunction "1_1") (pintype "passive"))
      (node (ref "U4") (pin "3") (pinfunction "IN+_3") (pintype "bidirectional"))
    )
    (net (code "60") (name "Net-(U4-IN-)") (class "Default")
      (node (ref "R28") (pin "2") (pinfunction "2_2") (pintype "passive"))
      (node (ref "R34") (pin "1") (pinfunction "1_1") (pintype "passive"))
      (node (ref "U4") (pin "1") (pinfunction "IN-_1") (pintype "bidirectional"))
    )
    (net (code "61") (name "Net-(µZ1B-LVDS_N_0)") (class "Default")
      (node (ref "R12") (pin "2") (pinfunction "2_2") (pintype "passive"))
      (node (ref "µZ1") (pin "13") (pinfunction "LVDS_N_0_13") (pintype "bidirectional"))
    )
    (net (code "62") (name "Net-(µZ1B-LVDS_N_1)") (class "Default")
      (node (ref "R14") (pin "2") (pinfunction "2_2") (pintype "passive"))
      (node (ref "µZ1") (pin "14") (pinfunction "LVDS_N_1_14") (pintype "bidirectional"))
    )
    (net (code "63") (name "Net-(µZ1B-LVDS_N_2)") (class "Default")
      (node (ref "R16") (pin "2") (pinfunction "2_2") (pintype "passive"))
      (node (ref "µZ1") (pin "19") (pinfunction "LVDS_N_2_19") (pintype "bidirectional"))
    )
    (net (code "64") (name "Net-(µZ1B-LVDS_N_3)") (class "Default")
      (node (ref "R18") (pin "2") (pinfunction "2_2") (pintype "passive"))
      (node (ref "µZ1") (pin "20") (pinfunction "LVDS_N_3_20") (pintype "bidirectional"))
    )
    (net (code "65") (name "Net-(µZ1B-LVDS_N_4)") (class "Default")
      (node (ref "R20") (pin "2") (pinfunction "2_2") (pintype "passive"))
      (node (ref "µZ1") (pin "25") (pinfunction "LVDS_N_4_25") (pintype "bidirectional"))
    )
    (net (code "66") (name "Net-(µZ1B-LVDS_N_5)") (class "Default")
      (node (ref "R22") (pin "2") (pinfunction "2_2") (pintype "passive"))
      (node (ref "µZ1") (pin "26") (pinfunction "LVDS_N_5_26") (pintype "bidirectional"))
    )
    (net (code "67") (name "Net-(µZ1B-LVDS_N_6)") (class "Default")
      (node (ref "R24") (pin "2") (pinfunction "2_2") (pintype "passive"))
      (node (ref "µZ1") (pin "31") (pinfunction "LVDS_N_6_31") (pintype "bidirectional"))
    )
    (net (code "68") (name "Net-(µZ1B-LVDS_N_7)") (class "Default")
      (node (ref "R26") (pin "2") (pinfunction "2_2") (pintype "passive"))
      (node (ref "µZ1") (pin "32") (pinfunction "LVDS_N_7_32") (pintype "bidirectional"))
    )
    (net (code "69") (name "Net-(µZ1B-LVDS_N_8)") (class "Default")
      (node (ref "R29") (pin "2") (pinfunction "2_2") (pintype "passive"))
      (node (ref "µZ1") (pin "37") (pinfunction "LVDS_N_8_37") (pintype "bidirectional"))
    )
    (net (code "70") (name "Net-(µZ1B-LVDS_N_9)") (class "Default")
      (node (ref "R31") (pin "2") (pinfunction "2_2") (pintype "passive"))
      (node (ref "µZ1") (pin "38") (pinfunction "LVDS_N_9_38") (pintype "bidirectional"))
    )
    (net (code "71") (name "Net-(µZ1B-LVDS_N_10)") (class "Default")
      (node (ref "R35") (pin "2") (pinfunction "2_2") (pintype "passive"))
      (node (ref "µZ1") (pin "43") (pinfunction "LVDS_N_10_43") (pintype "bidirectional"))
    )
    (net (code "72") (name "Net-(µZ1B-LVDS_N_11)") (class "Default")
      (node (ref "R37") (pin "2") (pinfunction "2_2") (pintype "passive"))
      (node (ref "µZ1") (pin "44") (pinfunction "LVDS_N_11_44") (pintype "bidirectional"))
    )
    (net (code "73") (name "Net-(µZ1B-LVDS_P_0)") (class "Default")
      (node (ref "R11") (pin "2") (pinfunction "2_2") (pintype "passive"))
      (node (ref "µZ1") (pin "11") (pinfunction "LVDS_P_0_11") (pintype "bidirectional"))
    )
    (net (code "74") (name "Net-(µZ1B-LVDS_P_1)") (class "Default")
      (node (ref "R13") (pin "2") (pinfunction "2_2") (pintype "passive"))
      (node (ref "µZ1") (pin "12") (pinfunction "LVDS_P_1_12") (pintype "bidirectional"))
    )
    (net (code "75") (name "Net-(µZ1B-LVDS_P_2)") (class "Default")
      (node (ref "R15") (pin "2") (pinfunction "2_2") (pintype "passive"))
      (node (ref "µZ1") (pin "17") (pinfunction "LVDS_P_2_17") (pintype "bidirectional"))
    )
    (net (code "76") (name "Net-(µZ1B-LVDS_P_3)") (class "Default")
      (node (ref "R17") (pin "2") (pinfunction "2_2") (pintype "passive"))
      (node (ref "µZ1") (pin "18") (pinfunction "LVDS_P_3_18") (pintype "bidirectional"))
    )
    (net (code "77") (name "Net-(µZ1B-LVDS_P_4)") (class "Default")
      (node (ref "R19") (pin "2") (pinfunction "2_2") (pintype "passive"))
      (node (ref "µZ1") (pin "23") (pinfunction "LVDS_P_4_23") (pintype "bidirectional"))
    )
    (net (code "78") (name "Net-(µZ1B-LVDS_P_5)") (class "Default")
      (node (ref "R21") (pin "2") (pinfunction "2_2") (pintype "passive"))
      (node (ref "µZ1") (pin "24") (pinfunction "LVDS_P_5_24") (pintype "bidirectional"))
    )
    (net (code "79") (name "Net-(µZ1B-LVDS_P_6)") (class "Default")
      (node (ref "R23") (pin "2") (pinfunction "2_2") (pintype "passive"))
      (node (ref "µZ1") (pin "29") (pinfunction "LVDS_P_6_29") (pintype "bidirectional"))
    )
    (net (code "80") (name "Net-(µZ1B-LVDS_P_7)") (class "Default")
      (node (ref "R25") (pin "2") (pinfunction "2_2") (pintype "passive"))
      (node (ref "µZ1") (pin "30") (pinfunction "LVDS_P_7_30") (pintype "bidirectional"))
    )
    (net (code "81") (name "Net-(µZ1B-LVDS_P_8)") (class "Default")
      (node (ref "R27") (pin "2") (pinfunction "2_2") (pintype "passive"))
      (node (ref "µZ1") (pin "35") (pinfunction "LVDS_P_8_35") (pintype "bidirectional"))
    )
    (net (code "82") (name "Net-(µZ1B-LVDS_P_9)") (class "Default")
      (node (ref "R30") (pin "2") (pinfunction "2_2") (pintype "passive"))
      (node (ref "µZ1") (pin "36") (pinfunction "LVDS_P_9_36") (pintype "bidirectional"))
    )
    (net (code "83") (name "Net-(µZ1B-LVDS_P_10)") (class "Default")
      (node (ref "R33") (pin "2") (pinfunction "2_2") (pintype "passive"))
      (node (ref "µZ1") (pin "41") (pinfunction "LVDS_P_10_41") (pintype "bidirectional"))
    )
    (net (code "84") (name "Net-(µZ1B-LVDS_P_11)") (class "Default")
      (node (ref "R36") (pin "2") (pinfunction "2_2") (pintype "passive"))
      (node (ref "µZ1") (pin "42") (pinfunction "LVDS_P_11_42") (pintype "bidirectional"))
    )
    (net (code "85") (name "Net-(µZ1E-PMOD_D1)") (class "Default")
      (node (ref "R1") (pin "2") (pinfunction "2_2") (pintype "passive"))
      (node (ref "µZ1") (pin "102") (pinfunction "PMOD_D1_102") (pintype "bidirectional"))
    )
    (net (code "86") (name "Net-(µZ1E-PMOD_D2)") (class "Default")
      (node (ref "R2") (pin "2") (pinfunction "2_2") (pintype "passive"))
      (node (ref "µZ1") (pin "103") (pinfunction "PMOD_D2_103") (pintype "bidirectional"))
    )
    (net (code "87") (name "Net-(µZ1E-PMOD_D6)") (class "Default")
      (node (ref "R3") (pin "2") (pinfunction "2_2") (pintype "passive"))
      (node (ref "µZ1") (pin "107") (pinfunction "PMOD_D6_107") (pintype "bidirectional"))
    )
    (net (code "88") (name "Net-(µZ1E-PMOD_D7)") (class "Default")
      (node (ref "R5") (pin "2") (pinfunction "2_2") (pintype "passive"))
      (node (ref "µZ1") (pin "108") (pinfunction "PMOD_D7_108") (pintype "bidirectional"))
    )
    (net (code "89") (name "PWR_EN") (class "Default")
      (node (ref "D5") (pin "3") (pinfunction "C_3") (pintype "passive"))
      (node (ref "R51") (pin "1") (pinfunction "1_1") (pintype "passive"))
      (node (ref "µZ1") (pin "5") (pinfunction "PWR_ENABLE_5") (pintype "input"))
    )
    (net (code "90") (name "V+") (class "Default")
      (node (ref "D1") (pin "1") (pinfunction "P$1_1") (pintype "bidirectional"))
      (node (ref "D1") (pin "2") (pinfunction "P$3_2") (pintype "bidirectional"))
      (node (ref "SW1") (pin "P$2") (pinfunction "P$2_P$2") (pintype "bidirectional"))
    )
    (net (code "91") (name "VADJ_EN") (class "Default")
      (node (ref "C15") (pin "1") (pinfunction "1_1") (pintype "passive"))
      (node (ref "R32") (pin "2") (pinfunction "2_2") (pintype "passive"))
      (node (ref "R39") (pin "2") (pinfunction "2_2") (pintype "passive"))
      (node (ref "U3") (pin "4") (pinfunction "EN_4") (pintype "input"))
      (node (ref "U4") (pin "4") (pinfunction "OUT_4") (pintype "bidirectional"))
    )
    (net (code "92") (name "VCCIO_EN") (class "Default")
      (node (ref "D4") (pin "3") (pinfunction "C_3") (pintype "passive"))
      (node (ref "R38") (pin "2") (pinfunction "2_2") (pintype "passive"))
      (node (ref "R46") (pin "1") (pinfunction "1_1") (pintype "passive"))
      (node (ref "µZ1") (pin "110") (pinfunction "PG_1V8_110") (pintype "input"))
    )
    (net (code "93") (name "Vd") (class "Default")
      (node (ref "C14") (pin "2") (pinfunction "2_2") (pintype "passive"))
      (node (ref "C3") (pin "1") (pinfunction "1_1") (pintype "passive"))
      (node (ref "C4") (pin "1") (pinfunction "1_1") (pintype "passive"))
      (node (ref "C6") (pin "2") (pinfunction "2_2") (pintype "passive"))
      (node (ref "C8") (pin "1") (pinfunction "1_1") (pintype "passive"))
      (node (ref "C9") (pin "1") (pinfunction "1_1") (pintype "passive"))
      (node (ref "D1") (pin "3") (pinfunction "P$2_3") (pintype "bidirectional"))
      (node (ref "R40") (pin "1") (pinfunction "1_1") (pintype "passive"))
      (node (ref "U2") (pin "7") (pinfunction "VIN_7") (pintype "power_in"))
      (node (ref "U4") (pin "5") (pinfunction "VCC_5") (pintype "bidirectional"))
    )
    (net (code "94") (name "unconnected-(U1-NC-Pad8)") (class "Default")
      (node (ref "U1") (pin "8") (pinfunction "NC_8") (pintype "no_connect"))
    )
    (net (code "95") (name "unconnected-(U1-NC_2-Pad5)") (class "Default")
      (node (ref "U1") (pin "5") (pinfunction "NC_2_5") (pintype "no_connect"))
    )
    (net (code "96") (name "unconnected-(U2-ENA-Pad5)") (class "Default")
      (node (ref "U2") (pin "5") (pinfunction "ENA_5") (pintype "input"))
    )
    (net (code "97") (name "unconnected-(U2-NC-Pad2)") (class "Default")
      (node (ref "U2") (pin "2") (pinfunction "NC_2") (pintype "no_connect"))
    )
    (net (code "98") (name "unconnected-(U2-NC_2-Pad3)") (class "Default")
      (node (ref "U2") (pin "3") (pinfunction "NC_2_3") (pintype "no_connect"))
    )
    (net (code "99") (name "unconnected-(X1-Pad1)") (class "Default")
      (node (ref "X1") (pin "1") (pinfunction "1_1") (pintype "passive"))
    )
    (net (code "100") (name "unconnected-(X1-Pad4)") (class "Default")
      (node (ref "X1") (pin "4") (pinfunction "4_4") (pintype "passive"))
    )
    (net (code "101") (name "unconnected-(X1-Pad5)") (class "Default")
      (node (ref "X1") (pin "5") (pinfunction "5_5") (pintype "passive"))
    )
    (net (code "102") (name "unconnected-(X1-Pad6)") (class "Default")
      (node (ref "X1") (pin "6") (pinfunction "6_6") (pintype "passive"))
    )
    (net (code "103") (name "unconnected-(X1-Pad8)") (class "Default")
      (node (ref "X1") (pin "8") (pinfunction "8_8") (pintype "passive"))
    )
    (net (code "104") (name "unconnected-(X1-Pad9)") (class "Default")
      (node (ref "X1") (pin "9") (pinfunction "9_9") (pintype "passive"))
    )
    (net (code "105") (name "unconnected-(µZ1B-LVDS_N_12-Pad49)") (class "Default")
      (node (ref "µZ1") (pin "49") (pinfunction "LVDS_N_12_49") (pintype "bidirectional"))
    )
    (net (code "106") (name "unconnected-(µZ1B-LVDS_N_13-Pad50)") (class "Default")
      (node (ref "µZ1") (pin "50") (pinfunction "LVDS_N_13_50") (pintype "bidirectional"))
    )
    (net (code "107") (name "unconnected-(µZ1B-LVDS_N_14-Pad55)") (class "Default")
      (node (ref "µZ1") (pin "55") (pinfunction "LVDS_N_14_55") (pintype "bidirectional"))
    )
    (net (code "108") (name "unconnected-(µZ1B-LVDS_N_15-Pad56)") (class "Default")
      (node (ref "µZ1") (pin "56") (pinfunction "LVDS_N_15_56") (pintype "bidirectional"))
    )
    (net (code "109") (name "unconnected-(µZ1B-LVDS_N_16-Pad63)") (class "Default")
      (node (ref "µZ1") (pin "63") (pinfunction "LVDS_N_16_63") (pintype "bidirectional"))
    )
    (net (code "110") (name "unconnected-(µZ1B-LVDS_N_17-Pad64)") (class "Default")
      (node (ref "µZ1") (pin "64") (pinfunction "LVDS_N_17_64") (pintype "bidirectional"))
    )
    (net (code "111") (name "unconnected-(µZ1B-LVDS_N_18-Pad69)") (class "Default")
      (node (ref "µZ1") (pin "69") (pinfunction "LVDS_N_18_69") (pintype "bidirectional"))
    )
    (net (code "112") (name "unconnected-(µZ1B-LVDS_N_19-Pad70)") (class "Default")
      (node (ref "µZ1") (pin "70") (pinfunction "LVDS_N_19_70") (pintype "bidirectional"))
    )
    (net (code "113") (name "unconnected-(µZ1B-LVDS_N_20-Pad75)") (class "Default")
      (node (ref "µZ1") (pin "75") (pinfunction "LVDS_N_20_75") (pintype "bidirectional"))
    )
    (net (code "114") (name "unconnected-(µZ1B-LVDS_N_21-Pad76)") (class "Default")
      (node (ref "µZ1") (pin "76") (pinfunction "LVDS_N_21_76") (pintype "bidirectional"))
    )
    (net (code "115") (name "unconnected-(µZ1B-LVDS_N_22-Pad83)") (class "Default")
      (node (ref "µZ1") (pin "83") (pinfunction "LVDS_N_22_83") (pintype "bidirectional"))
    )
    (net (code "116") (name "unconnected-(µZ1B-LVDS_N_23-Pad84)") (class "Default")
      (node (ref "µZ1") (pin "84") (pinfunction "LVDS_N_23_84") (pintype "bidirectional"))
    )
    (net (code "117") (name "unconnected-(µZ1B-LVDS_P_12-Pad47)") (class "Default")
      (node (ref "µZ1") (pin "47") (pinfunction "LVDS_P_12_47") (pintype "bidirectional"))
    )
    (net (code "118") (name "unconnected-(µZ1B-LVDS_P_13-Pad48)") (class "Default")
      (node (ref "µZ1") (pin "48") (pinfunction "LVDS_P_13_48") (pintype "bidirectional"))
    )
    (net (code "119") (name "unconnected-(µZ1B-LVDS_P_14-Pad53)") (class "Default")
      (node (ref "µZ1") (pin "53") (pinfunction "LVDS_P_14_53") (pintype "bidirectional"))
    )
    (net (code "120") (name "unconnected-(µZ1B-LVDS_P_15-Pad54)") (class "Default")
      (node (ref "µZ1") (pin "54") (pinfunction "LVDS_P_15_54") (pintype "bidirectional"))
    )
    (net (code "121") (name "unconnected-(µZ1B-LVDS_P_16-Pad61)") (class "Default")
      (node (ref "µZ1") (pin "61") (pinfunction "LVDS_P_16_61") (pintype "bidirectional"))
    )
    (net (code "122") (name "unconnected-(µZ1B-LVDS_P_17-Pad62)") (class "Default")
      (node (ref "µZ1") (pin "62") (pinfunction "LVDS_P_17_62") (pintype "bidirectional"))
    )
    (net (code "123") (name "unconnected-(µZ1B-LVDS_P_18-Pad67)") (class "Default")
      (node (ref "µZ1") (pin "67") (pinfunction "LVDS_P_18_67") (pintype "bidirectional"))
    )
    (net (code "124") (name "unconnected-(µZ1B-LVDS_P_19-Pad68)") (class "Default")
      (node (ref "µZ1") (pin "68") (pinfunction "LVDS_P_19_68") (pintype "bidirectional"))
    )
    (net (code "125") (name "unconnected-(µZ1B-LVDS_P_20-Pad73)") (class "Default")
      (node (ref "µZ1") (pin "73") (pinfunction "LVDS_P_20_73") (pintype "bidirectional"))
    )
    (net (code "126") (name "unconnected-(µZ1B-LVDS_P_21-Pad74)") (class "Default")
      (node (ref "µZ1") (pin "74") (pinfunction "LVDS_P_21_74") (pintype "bidirectional"))
    )
    (net (code "127") (name "unconnected-(µZ1B-LVDS_P_22-Pad81)") (class "Default")
      (node (ref "µZ1") (pin "81") (pinfunction "LVDS_P_22_81") (pintype "bidirectional"))
    )
    (net (code "128") (name "unconnected-(µZ1B-LVDS_P_23-Pad82)") (class "Default")
      (node (ref "µZ1") (pin "82") (pinfunction "LVDS_P_23_82") (pintype "bidirectional"))
    )
    (net (code "129") (name "unconnected-(µZ1C-BANK13_LVDS_0_N-Pad89)") (class "Default")
      (node (ref "µZ1") (pin "89") (pinfunction "BANK13_LVDS_0_N_89") (pintype "output"))
    )
    (net (code "130") (name "unconnected-(µZ1C-BANK13_LVDS_0_P-Pad87)") (class "Default")
      (node (ref "µZ1") (pin "87") (pinfunction "BANK13_LVDS_0_P_87") (pintype "output"))
    )
    (net (code "131") (name "unconnected-(µZ1C-BANK13_LVDS_1_N-Pad90)") (class "Default")
      (node (ref "µZ1") (pin "90") (pinfunction "BANK13_LVDS_1_N_90") (pintype "output"))
    )
    (net (code "132") (name "unconnected-(µZ1C-BANK13_LVDS_1_P-Pad88)") (class "Default")
      (node (ref "µZ1") (pin "88") (pinfunction "BANK13_LVDS_1_P_88") (pintype "output"))
    )
    (net (code "133") (name "unconnected-(µZ1C-BANK13_LVDS_2_N-Pad93)") (class "Default")
      (node (ref "µZ1") (pin "93") (pinfunction "BANK13_LVDS_2_N_93") (pintype "output"))
    )
    (net (code "134") (name "unconnected-(µZ1C-BANK13_LVDS_2_P-Pad91)") (class "Default")
      (node (ref "µZ1") (pin "91") (pinfunction "BANK13_LVDS_2_P_91") (pintype "output"))
    )
    (net (code "135") (name "unconnected-(µZ1C-BANK13_LVDS_3_N-Pad94)") (class "Default")
      (node (ref "µZ1") (pin "94") (pinfunction "BANK13_LVDS_3_N_94") (pintype "output"))
    )
    (net (code "136") (name "unconnected-(µZ1C-BANK13_LVDS_3_P-Pad92)") (class "Default")
      (node (ref "µZ1") (pin "92") (pinfunction "BANK13_LVDS_3_P_92") (pintype "output"))
    )
    (net (code "137") (name "unconnected-(µZ1C-DXP_0_N-Pad100)") (class "Default")
      (node (ref "µZ1") (pin "100") (pinfunction "DXP_0_N_100") (pintype "output"))
    )
    (net (code "138") (name "unconnected-(µZ1C-DXP_0_P-Pad98)") (class "Default")
      (node (ref "µZ1") (pin "98") (pinfunction "DXP_0_P_98") (pintype "output"))
    )
    (net (code "139") (name "unconnected-(µZ1C-FPGA_DONE-Pad8)") (class "Default")
      (node (ref "µZ1") (pin "8") (pinfunction "FPGA_DONE_8") (pintype "output"))
    )
    (net (code "140") (name "unconnected-(µZ1C-JTAG_TCK-Pad1)") (class "Default")
      (node (ref "µZ1") (pin "1") (pinfunction "JTAG_TCK_1") (pintype "input"))
    )
    (net (code "141") (name "unconnected-(µZ1C-JTAG_TDI-Pad4)") (class "Default")
      (node (ref "µZ1") (pin "4") (pinfunction "JTAG_TDI_4") (pintype "input"))
    )
    (net (code "142") (name "unconnected-(µZ1C-JTAG_TDO-Pad3)") (class "Default")
      (node (ref "µZ1") (pin "3") (pinfunction "JTAG_TDO_3") (pintype "output"))
    )
    (net (code "143") (name "unconnected-(µZ1C-JTAG_TMS-Pad2)") (class "Default")
      (node (ref "µZ1") (pin "2") (pinfunction "JTAG_TMS_2") (pintype "input"))
    )
    (net (code "144") (name "unconnected-(µZ1C-SE_0-Pad9)") (class "Default")
      (node (ref "µZ1") (pin "9") (pinfunction "SE_0_9") (pintype "bidirectional"))
    )
    (net (code "145") (name "unconnected-(µZ1C-SE_1-Pad10)") (class "Default")
      (node (ref "µZ1") (pin "10") (pinfunction "SE_1_10") (pintype "bidirectional"))
    )
    (net (code "146") (name "unconnected-(µZ1C-VP_0_N-Pad99)") (class "Default")
      (node (ref "µZ1") (pin "99") (pinfunction "VP_0_N_99") (pintype "output"))
    )
    (net (code "147") (name "unconnected-(µZ1C-VP_0_P-Pad97)") (class "Default")
      (node (ref "µZ1") (pin "97") (pinfunction "VP_0_P_97") (pintype "output"))
    )
    (net (code "148") (name "unconnected-(µZ1C-~{CARRIER_SRST}-Pad6)") (class "Default")
      (node (ref "µZ1") (pin "6") (pinfunction "~{CARRIER_SRST}_6") (pintype "output"))
    )
    (net (code "149") (name "unconnected-(µZ1D-LVDS_N_0-Pad119)") (class "Default")
      (node (ref "µZ1") (pin "119") (pinfunction "LVDS_N_0_119") (pintype "bidirectional"))
    )
    (net (code "150") (name "unconnected-(µZ1D-LVDS_N_1-Pad120)") (class "Default")
      (node (ref "µZ1") (pin "120") (pinfunction "LVDS_N_1_120") (pintype "bidirectional"))
    )
    (net (code "151") (name "unconnected-(µZ1D-LVDS_N_2-Pad125)") (class "Default")
      (node (ref "µZ1") (pin "125") (pinfunction "LVDS_N_2_125") (pintype "bidirectional"))
    )
    (net (code "152") (name "unconnected-(µZ1D-LVDS_N_3-Pad126)") (class "Default")
      (node (ref "µZ1") (pin "126") (pinfunction "LVDS_N_3_126") (pintype "bidirectional"))
    )
    (net (code "153") (name "unconnected-(µZ1D-LVDS_N_4-Pad131)") (class "Default")
      (node (ref "µZ1") (pin "131") (pinfunction "LVDS_N_4_131") (pintype "bidirectional"))
    )
    (net (code "154") (name "unconnected-(µZ1D-LVDS_N_5-Pad132)") (class "Default")
      (node (ref "µZ1") (pin "132") (pinfunction "LVDS_N_5_132") (pintype "bidirectional"))
    )
    (net (code "155") (name "unconnected-(µZ1D-LVDS_N_6-Pad137)") (class "Default")
      (node (ref "µZ1") (pin "137") (pinfunction "LVDS_N_6_137") (pintype "bidirectional"))
    )
    (net (code "156") (name "unconnected-(µZ1D-LVDS_N_7-Pad138)") (class "Default")
      (node (ref "µZ1") (pin "138") (pinfunction "LVDS_N_7_138") (pintype "bidirectional"))
    )
    (net (code "157") (name "unconnected-(µZ1D-LVDS_N_9-Pad144)") (class "Default")
      (node (ref "µZ1") (pin "144") (pinfunction "LVDS_N_9_144") (pintype "bidirectional"))
    )
    (net (code "158") (name "unconnected-(µZ1D-LVDS_N_11-Pad150)") (class "Default")
      (node (ref "µZ1") (pin "150") (pinfunction "LVDS_N_11_150") (pintype "bidirectional"))
    )
    (net (code "159") (name "unconnected-(µZ1D-LVDS_N_12-Pad155)") (class "Default")
      (node (ref "µZ1") (pin "155") (pinfunction "LVDS_N_12_155") (pintype "bidirectional"))
    )
    (net (code "160") (name "unconnected-(µZ1D-LVDS_N_13-Pad156)") (class "Default")
      (node (ref "µZ1") (pin "156") (pinfunction "LVDS_N_13_156") (pintype "bidirectional"))
    )
    (net (code "161") (name "unconnected-(µZ1D-LVDS_N_14-Pad163)") (class "Default")
      (node (ref "µZ1") (pin "163") (pinfunction "LVDS_N_14_163") (pintype "bidirectional"))
    )
    (net (code "162") (name "unconnected-(µZ1D-LVDS_N_15-Pad164)") (class "Default")
      (node (ref "µZ1") (pin "164") (pinfunction "LVDS_N_15_164") (pintype "bidirectional"))
    )
    (net (code "163") (name "unconnected-(µZ1D-LVDS_N_16-Pad169)") (class "Default")
      (node (ref "µZ1") (pin "169") (pinfunction "LVDS_N_16_169") (pintype "bidirectional"))
    )
    (net (code "164") (name "unconnected-(µZ1D-LVDS_N_17-Pad170)") (class "Default")
      (node (ref "µZ1") (pin "170") (pinfunction "LVDS_N_17_170") (pintype "bidirectional"))
    )
    (net (code "165") (name "unconnected-(µZ1D-LVDS_N_18-Pad175)") (class "Default")
      (node (ref "µZ1") (pin "175") (pinfunction "LVDS_N_18_175") (pintype "bidirectional"))
    )
    (net (code "166") (name "unconnected-(µZ1D-LVDS_N_19-Pad176)") (class "Default")
      (node (ref "µZ1") (pin "176") (pinfunction "LVDS_N_19_176") (pintype "bidirectional"))
    )
    (net (code "167") (name "unconnected-(µZ1D-LVDS_N_20-Pad183)") (class "Default")
      (node (ref "µZ1") (pin "183") (pinfunction "LVDS_N_20_183") (pintype "bidirectional"))
    )
    (net (code "168") (name "unconnected-(µZ1D-LVDS_N_21-Pad184)") (class "Default")
      (node (ref "µZ1") (pin "184") (pinfunction "LVDS_N_21_184") (pintype "bidirectional"))
    )
    (net (code "169") (name "unconnected-(µZ1D-LVDS_N_22-Pad189)") (class "Default")
      (node (ref "µZ1") (pin "189") (pinfunction "LVDS_N_22_189") (pintype "bidirectional"))
    )
    (net (code "170") (name "unconnected-(µZ1D-LVDS_N_23-Pad190)") (class "Default")
      (node (ref "µZ1") (pin "190") (pinfunction "LVDS_N_23_190") (pintype "bidirectional"))
    )
    (net (code "171") (name "unconnected-(µZ1D-LVDS_P_0-Pad117)") (class "Default")
      (node (ref "µZ1") (pin "117") (pinfunction "LVDS_P_0_117") (pintype "bidirectional"))
    )
    (net (code "172") (name "unconnected-(µZ1D-LVDS_P_1-Pad118)") (class "Default")
      (node (ref "µZ1") (pin "118") (pinfunction "LVDS_P_1_118") (pintype "bidirectional"))
    )
    (net (code "173") (name "unconnected-(µZ1D-LVDS_P_2-Pad123)") (class "Default")
      (node (ref "µZ1") (pin "123") (pinfunction "LVDS_P_2_123") (pintype "bidirectional"))
    )
    (net (code "174") (name "unconnected-(µZ1D-LVDS_P_3-Pad124)") (class "Default")
      (node (ref "µZ1") (pin "124") (pinfunction "LVDS_P_3_124") (pintype "bidirectional"))
    )
    (net (code "175") (name "unconnected-(µZ1D-LVDS_P_4-Pad129)") (class "Default")
      (node (ref "µZ1") (pin "129") (pinfunction "LVDS_P_4_129") (pintype "bidirectional"))
    )
    (net (code "176") (name "unconnected-(µZ1D-LVDS_P_5-Pad130)") (class "Default")
      (node (ref "µZ1") (pin "130") (pinfunction "LVDS_P_5_130") (pintype "bidirectional"))
    )
    (net (code "177") (name "unconnected-(µZ1D-LVDS_P_6-Pad135)") (class "Default")
      (node (ref "µZ1") (pin "135") (pinfunction "LVDS_P_6_135") (pintype "bidirectional"))
    )
    (net (code "178") (name "unconnected-(µZ1D-LVDS_P_7-Pad136)") (class "Default")
      (node (ref "µZ1") (pin "136") (pinfunction "LVDS_P_7_136") (pintype "bidirectional"))
    )
    (net (code "179") (name "unconnected-(µZ1D-LVDS_P_9-Pad142)") (class "Default")
      (node (ref "µZ1") (pin "142") (pinfunction "LVDS_P_9_142") (pintype "bidirectional"))
    )
    (net (code "180") (name "unconnected-(µZ1D-LVDS_P_11-Pad148)") (class "Default")
      (node (ref "µZ1") (pin "148") (pinfunction "LVDS_P_11_148") (pintype "bidirectional"))
    )
    (net (code "181") (name "unconnected-(µZ1D-LVDS_P_12-Pad153)") (class "Default")
      (node (ref "µZ1") (pin "153") (pinfunction "LVDS_P_12_153") (pintype "bidirectional"))
    )
    (net (code "182") (name "unconnected-(µZ1D-LVDS_P_13-Pad154)") (class "Default")
      (node (ref "µZ1") (pin "154") (pinfunction "LVDS_P_13_154") (pintype "bidirectional"))
    )
    (net (code "183") (name "unconnected-(µZ1D-LVDS_P_14-Pad161)") (class "Default")
      (node (ref "µZ1") (pin "161") (pinfunction "LVDS_P_14_161") (pintype "bidirectional"))
    )
    (net (code "184") (name "unconnected-(µZ1D-LVDS_P_15-Pad162)") (class "Default")
      (node (ref "µZ1") (pin "162") (pinfunction "LVDS_P_15_162") (pintype "bidirectional"))
    )
    (net (code "185") (name "unconnected-(µZ1D-LVDS_P_16-Pad167)") (class "Default")
      (node (ref "µZ1") (pin "167") (pinfunction "LVDS_P_16_167") (pintype "bidirectional"))
    )
    (net (code "186") (name "unconnected-(µZ1D-LVDS_P_17-Pad168)") (class "Default")
      (node (ref "µZ1") (pin "168") (pinfunction "LVDS_P_17_168") (pintype "bidirectional"))
    )
    (net (code "187") (name "unconnected-(µZ1D-LVDS_P_18-Pad173)") (class "Default")
      (node (ref "µZ1") (pin "173") (pinfunction "LVDS_P_18_173") (pintype "bidirectional"))
    )
    (net (code "188") (name "unconnected-(µZ1D-LVDS_P_19-Pad174)") (class "Default")
      (node (ref "µZ1") (pin "174") (pinfunction "LVDS_P_19_174") (pintype "bidirectional"))
    )
    (net (code "189") (name "unconnected-(µZ1D-LVDS_P_20-Pad181)") (class "Default")
      (node (ref "µZ1") (pin "181") (pinfunction "LVDS_P_20_181") (pintype "bidirectional"))
    )
    (net (code "190") (name "unconnected-(µZ1D-LVDS_P_21-Pad182)") (class "Default")
      (node (ref "µZ1") (pin "182") (pinfunction "LVDS_P_21_182") (pintype "bidirectional"))
    )
    (net (code "191") (name "unconnected-(µZ1D-LVDS_P_22-Pad187)") (class "Default")
      (node (ref "µZ1") (pin "187") (pinfunction "LVDS_P_22_187") (pintype "bidirectional"))
    )
    (net (code "192") (name "unconnected-(µZ1D-LVDS_P_23-Pad188)") (class "Default")
      (node (ref "µZ1") (pin "188") (pinfunction "LVDS_P_23_188") (pintype "bidirectional"))
    )
    (net (code "193") (name "unconnected-(µZ1E-BANK13_LVDS_4_N-Pad195)") (class "Default")
      (node (ref "µZ1") (pin "195") (pinfunction "BANK13_LVDS_4_N_195") (pintype "bidirectional"))
    )
    (net (code "194") (name "unconnected-(µZ1E-BANK13_LVDS_4_P-Pad193)") (class "Default")
      (node (ref "µZ1") (pin "193") (pinfunction "BANK13_LVDS_4_P_193") (pintype "bidirectional"))
    )
    (net (code "195") (name "unconnected-(µZ1E-BANK13_LVDS_5_N-Pad196)") (class "Default")
      (node (ref "µZ1") (pin "196") (pinfunction "BANK13_LVDS_5_N_196") (pintype "bidirectional"))
    )
    (net (code "196") (name "unconnected-(µZ1E-BANK13_LVDS_5_P-Pad194)") (class "Default")
      (node (ref "µZ1") (pin "194") (pinfunction "BANK13_LVDS_5_P_194") (pintype "bidirectional"))
    )
    (net (code "197") (name "unconnected-(µZ1E-BANK13_LVDS_6_N-Pad199)") (class "Default")
      (node (ref "µZ1") (pin "199") (pinfunction "BANK13_LVDS_6_N_199") (pintype "bidirectional"))
    )
    (net (code "198") (name "unconnected-(µZ1E-BANK13_LVDS_6_P-Pad197)") (class "Default")
      (node (ref "µZ1") (pin "197") (pinfunction "BANK13_LVDS_6_P_197") (pintype "bidirectional"))
    )
    (net (code "199") (name "unconnected-(µZ1E-BANK13_SE_0-Pad200)") (class "Default")
      (node (ref "µZ1") (pin "200") (pinfunction "BANK13_SE_0_200") (pintype "bidirectional"))
    )
    (net (code "200") (name "unconnected-(µZ1E-PG_MODULE-Pad111)") (class "Default")
      (node (ref "µZ1") (pin "111") (pinfunction "PG_MODULE_111") (pintype "output"))
    )
    (net (code "201") (name "unconnected-(µZ1E-PMOD_D0-Pad101)") (class "Default")
      (node (ref "µZ1") (pin "101") (pinfunction "PMOD_D0_101") (pintype "bidirectional"))
    )
    (net (code "202") (name "unconnected-(µZ1E-PMOD_D3-Pad104)") (class "Default")
      (node (ref "µZ1") (pin "104") (pinfunction "PMOD_D3_104") (pintype "bidirectional"))
    )
    (net (code "203") (name "unconnected-(µZ1E-PMOD_D4-Pad105)") (class "Default")
      (node (ref "µZ1") (pin "105") (pinfunction "PMOD_D4_105") (pintype "bidirectional"))
    )
    (net (code "204") (name "unconnected-(µZ1E-PMOD_D5-Pad106)") (class "Default")
      (node (ref "µZ1") (pin "106") (pinfunction "PMOD_D5_106") (pintype "bidirectional"))
    )
    (net (code "205") (name "unconnected-(µZ1E-SE_0-Pad113)") (class "Default")
      (node (ref "µZ1") (pin "113") (pinfunction "SE_0_113") (pintype "bidirectional"))
    )
    (net (code "206") (name "unconnected-(µZ1E-SE_1-Pad114)") (class "Default")
      (node (ref "µZ1") (pin "114") (pinfunction "SE_1_114") (pintype "bidirectional"))
    )
    (net (code "207") (name "unconnected-(µZ1E-~{INIT}-Pad109)") (class "Default")
      (node (ref "µZ1") (pin "109") (pinfunction "~{INIT}_109") (pintype "input"))
    )
  )
)
